# Solar_Charger_Board.net
KiCad netlist of a schematic drawn in EAGLE
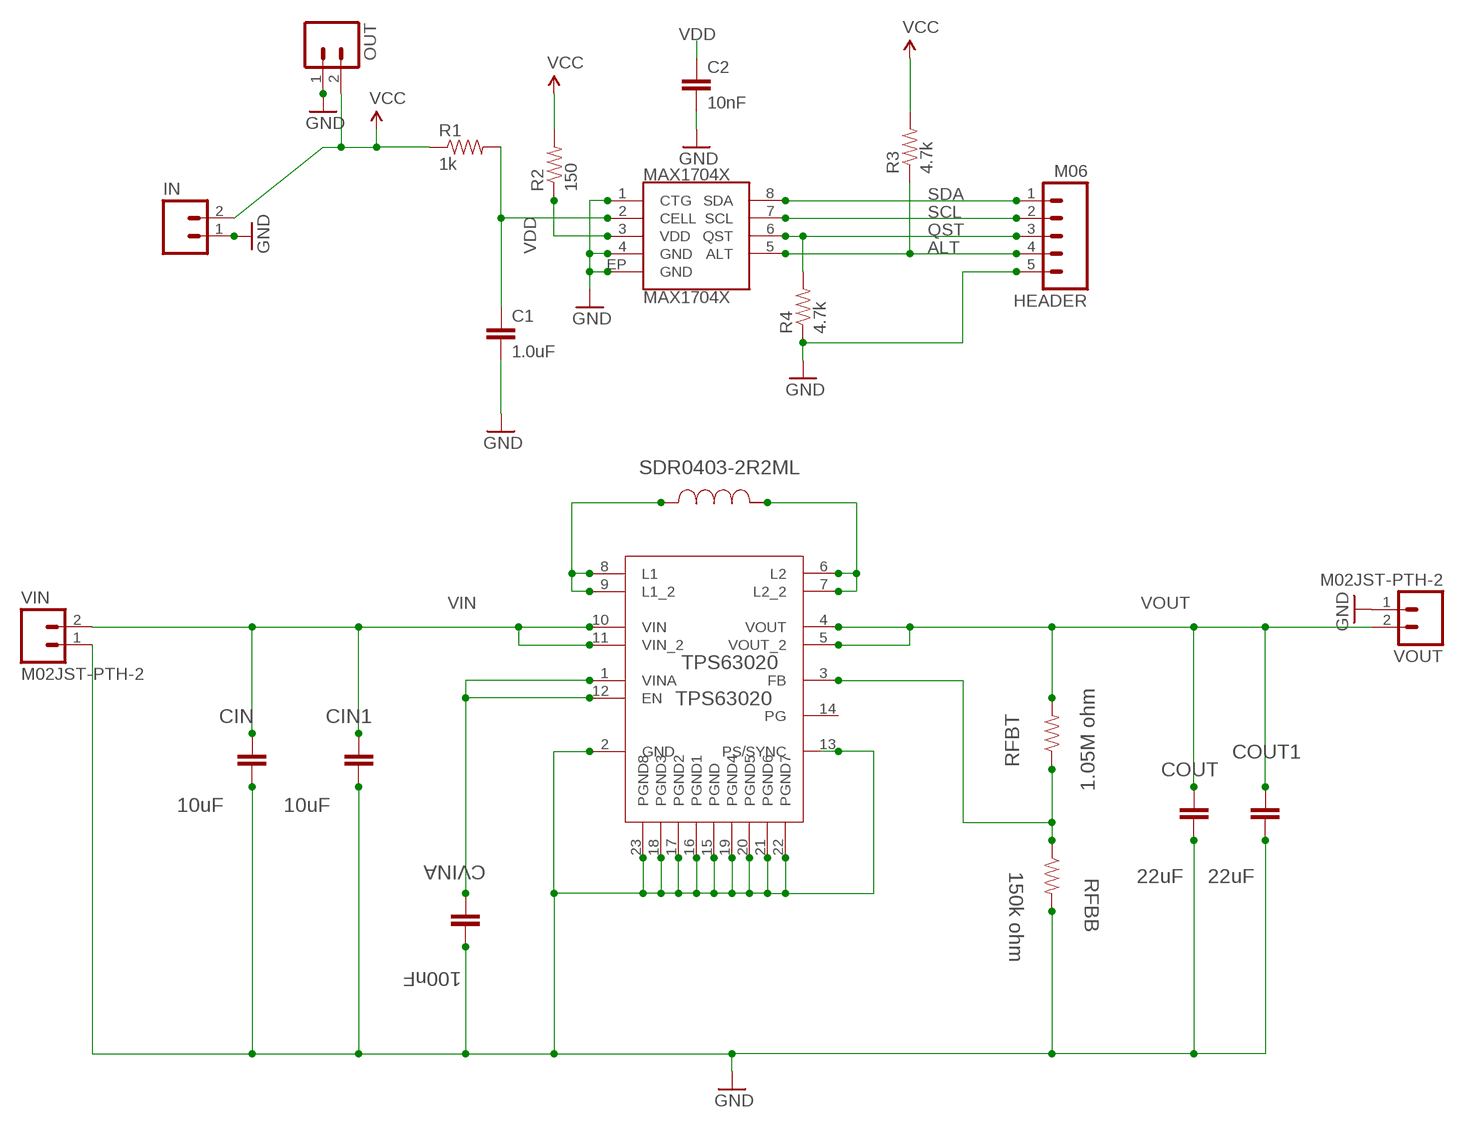
[diagram p0: schematic, sheet 1]

(export (version "E")
  (design (tool "Eeschema 10.0.6"))
  (components
    (comp (ref "C1")
      (value "1.0uF")
      (footprint "eagle-import:0805")
      (libsource (lib "eagle-import") (part "1.0UF-25V-+80/-20(0805)"))
    )
    (comp (ref "C2")
      (value "10nF")
      (footprint "eagle-import:0805")
      (libsource (lib "eagle-import") (part "2.2UF-25V-+80/-20(0805)"))
    )
    (comp (ref "CIN")
      (value "10uF")
      (footprint "eagle-import:0805")
      (libsource (lib "eagle-import") (part "CAP0805"))
    )
    (comp (ref "CIN1")
      (value "10uF")
      (footprint "eagle-import:0805")
      (libsource (lib "eagle-import") (part "CAP0805"))
    )
    (comp (ref "COUT")
      (value "22uF")
      (footprint "eagle-import:0805")
      (libsource (lib "eagle-import") (part "CAP0805"))
    )
    (comp (ref "COUT1")
      (value "22uF")
      (footprint "eagle-import:0805")
      (libsource (lib "eagle-import") (part "CAP0805"))
    )
    (comp (ref "CVINA")
      (value "100nF")
      (footprint "eagle-import:0805")
      (libsource (lib "eagle-import") (part "CAP0805"))
    )
    (comp (ref "HEADER")
      (value "M06")
      (footprint "eagle-import:1X05")
      (libsource (lib "eagle-import") (part "M05PTH"))
    )
    (comp (ref "IN")
      (value "input")
      (footprint "eagle-import:JST-2-PTH")
      (libsource (lib "eagle-import") (part "M02JST-PTH-2"))
    )
    (comp (ref "L1")
      (value "SDR0403-2R2ML")
      (footprint "eagle-import:SDR0403")
      (libsource (lib "eagle-import") (part "SDR0403-2R2ML"))
    )
    (comp (ref "MAX1704X")
      (value "MAX1704X")
      (footprint "eagle-import:TDFN-8")
      (libsource (lib "eagle-import") (part "MAX1704X"))
    )
    (comp (ref "OUT")
      (value "M02JST-PTH-2")
      (footprint "eagle-import:JST-2-PTH")
      (libsource (lib "eagle-import") (part "M02JST-PTH-2"))
    )
    (comp (ref "R1")
      (value "1k")
      (footprint "eagle-import:0805")
      (libsource (lib "eagle-import") (part "RESISTOR0805-RES"))
    )
    (comp (ref "R2")
      (value "150")
      (footprint "eagle-import:0805")
      (libsource (lib "eagle-import") (part "RESISTOR0805-RES"))
    )
    (comp (ref "R3")
      (value "4.7k")
      (footprint "eagle-import:0805")
      (libsource (lib "eagle-import") (part "RESISTOR0805-RES"))
    )
    (comp (ref "R4")
      (value "4.7k")
      (footprint "eagle-import:0805")
      (libsource (lib "eagle-import") (part "RESISTOR0805-RES"))
    )
    (comp (ref "RFBB")
      (value "150k ohm")
      (footprint "eagle-import:0805")
      (libsource (lib "eagle-import") (part "RESISTOR0805-RES"))
    )
    (comp (ref "RFBT")
      (value "1.05M ohm")
      (footprint "eagle-import:0805")
      (libsource (lib "eagle-import") (part "RESISTOR0805-RES"))
    )
    (comp (ref "TPS63020")
      (value "TPS63020")
      (footprint "eagle-import:QFN14-3X4MM")
      (libsource (lib "eagle-import") (part "TPS63020"))
    )
    (comp (ref "VIN")
      (value "M02JST-PTH-2")
      (footprint "eagle-import:JST-2-PTH")
      (libsource (lib "eagle-import") (part "M02JST-PTH-2"))
    )
    (comp (ref "VOUT")
      (value "M02JST-PTH-2")
      (footprint "eagle-import:JST-2-PTH")
      (libsource (lib "eagle-import") (part "M02JST-PTH-2"))
    )
  )
  (nets
    (net (code "1") (name "/ALT") (class "Default")
      (node (ref "HEADER") (pin "4") (pinfunction "4_4") (pintype "passive"))
      (node (ref "MAX1704X") (pin "5") (pinfunction "ALT_5") (pintype "bidirectional"))
      (node (ref "R3") (pin "1") (pinfunction "1_1") (pintype "passive"))
    )
    (net (code "2") (name "/QST") (class "Default")
      (node (ref "HEADER") (pin "3") (pinfunction "3_3") (pintype "passive"))
      (node (ref "MAX1704X") (pin "6") (pinfunction "QST_6") (pintype "bidirectional"))
      (node (ref "R4") (pin "2") (pinfunction "2_2") (pintype "passive"))
    )
    (net (code "3") (name "/SCL") (class "Default")
      (node (ref "HEADER") (pin "2") (pinfunction "2_2") (pintype "passive"))
      (node (ref "MAX1704X") (pin "7") (pinfunction "SCL_7") (pintype "bidirectional"))
    )
    (net (code "4") (name "/SDA") (class "Default")
      (node (ref "HEADER") (pin "1") (pinfunction "1_1") (pintype "passive"))
      (node (ref "MAX1704X") (pin "8") (pinfunction "SDA_8") (pintype "bidirectional"))
    )
    (net (code "5") (name "/VDD") (class "Default")
      (node (ref "C2") (pin "1") (pinfunction "1_1") (pintype "passive"))
      (node (ref "MAX1704X") (pin "3") (pinfunction "VDD_3") (pintype "bidirectional"))
      (node (ref "R2") (pin "1") (pinfunction "1_1") (pintype "passive"))
    )
    (net (code "6") (name "/VIN") (class "Default")
      (node (ref "CIN") (pin "1") (pinfunction "1_1") (pintype "passive"))
      (node (ref "CIN1") (pin "1") (pinfunction "1_1") (pintype "passive"))
      (node (ref "TPS63020") (pin "10") (pinfunction "VIN_10") (pintype "bidirectional"))
      (node (ref "TPS63020") (pin "11") (pinfunction "VIN_2_11") (pintype "bidirectional"))
      (node (ref "VIN") (pin "2") (pinfunction "2_2") (pintype "passive"))
    )
    (net (code "7") (name "/VOUT") (class "Default")
      (node (ref "COUT") (pin "1") (pinfunction "1_1") (pintype "passive"))
      (node (ref "COUT1") (pin "1") (pinfunction "1_1") (pintype "passive"))
      (node (ref "RFBT") (pin "2") (pinfunction "2_2") (pintype "passive"))
      (node (ref "TPS63020") (pin "4") (pinfunction "VOUT_4") (pintype "bidirectional"))
      (node (ref "TPS63020") (pin "5") (pinfunction "VOUT_2_5") (pintype "bidirectional"))
      (node (ref "VOUT") (pin "2") (pinfunction "2_2") (pintype "passive"))
    )
    (net (code "8") (name "GND") (class "Default")
      (node (ref "C1") (pin "2") (pinfunction "2_2") (pintype "passive"))
      (node (ref "C2") (pin "2") (pinfunction "2_2") (pintype "passive"))
      (node (ref "CIN") (pin "2") (pinfunction "2_2") (pintype "passive"))
      (node (ref "CIN1") (pin "2") (pinfunction "2_2") (pintype "passive"))
      (node (ref "COUT") (pin "2") (pinfunction "2_2") (pintype "passive"))
      (node (ref "COUT1") (pin "2") (pinfunction "2_2") (pintype "passive"))
      (node (ref "CVINA") (pin "2") (pinfunction "2_2") (pintype "passive"))
      (node (ref "HEADER") (pin "5") (pinfunction "5_5") (pintype "passive"))
      (node (ref "IN") (pin "1") (pinfunction "1_1") (pintype "passive"))
      (node (ref "MAX1704X") (pin "1") (pinfunction "CTG_1") (pintype "bidirectional"))
      (node (ref "MAX1704X") (pin "4") (pinfunction "GND_4") (pintype "bidirectional"))
      (node (ref "MAX1704X") (pin "EP") (pinfunction "GND_EP") (pintype "bidirectional"))
      (node (ref "OUT") (pin "1") (pinfunction "1_1") (pintype "passive"))
      (node (ref "R4") (pin "1") (pinfunction "1_1") (pintype "passive"))
      (node (ref "RFBB") (pin "2") (pinfunction "2_2") (pintype "passive"))
      (node (ref "TPS63020") (pin "13") (pinfunction "PS/SYNC_13") (pintype "bidirectional"))
      (node (ref "TPS63020") (pin "15") (pinfunction "PGND_15") (pintype "bidirectional"))
      (node (ref "TPS63020") (pin "16") (pinfunction "PGND1_16") (pintype "bidirectional"))
      (node (ref "TPS63020") (pin "17") (pinfunction "PGND2_17") (pintype "bidirectional"))
      (node (ref "TPS63020") (pin "18") (pinfunction "PGND3_18") (pintype "bidirectional"))
      (node (ref "TPS63020") (pin "19") (pinfunction "PGND4_19") (pintype "bidirectional"))
      (node (ref "TPS63020") (pin "2") (pinfunction "GND_2") (pintype "bidirectional"))
      (node (ref "TPS63020") (pin "20") (pinfunction "PGND5_20") (pintype "bidirectional"))
      (node (ref "TPS63020") (pin "21") (pinfunction "PGND6_21") (pintype "bidirectional"))
      (node (ref "TPS63020") (pin "22") (pinfunction "PGND7_22") (pintype "bidirectional"))
      (node (ref "TPS63020") (pin "23") (pinfunction "PGND8_23") (pintype "bidirectional"))
      (node (ref "VIN") (pin "1") (pinfunction "1_1") (pintype "passive"))
      (node (ref "VOUT") (pin "1") (pinfunction "1_1") (pintype "passive"))
    )
    (net (code "9") (name "Net-(MAX1704X-CELL)") (class "Default")
      (node (ref "C1") (pin "1") (pinfunction "1_1") (pintype "passive"))
      (node (ref "MAX1704X") (pin "2") (pinfunction "CELL_2") (pintype "bidirectional"))
      (node (ref "R1") (pin "2") (pinfunction "2_2") (pintype "passive"))
    )
    (net (code "10") (name "Net-(TPS63020-EN)") (class "Default")
      (node (ref "CVINA") (pin "1") (pinfunction "1_1") (pintype "passive"))
      (node (ref "TPS63020") (pin "1") (pinfunction "VINA_1") (pintype "bidirectional"))
      (node (ref "TPS63020") (pin "12") (pinfunction "EN_12") (pintype "bidirectional"))
    )
    (net (code "11") (name "Net-(TPS63020-FB)") (class "Default")
      (node (ref "RFBB") (pin "1") (pinfunction "1_1") (pintype "passive"))
      (node (ref "RFBT") (pin "1") (pinfunction "1_1") (pintype "passive"))
      (node (ref "TPS63020") (pin "3") (pinfunction "FB_3") (pintype "bidirectional"))
    )
    (net (code "12") (name "Net-(TPS63020-L1)") (class "Default")
      (node (ref "L1") (pin "1") (pinfunction "1_1") (pintype "passive"))
      (node (ref "TPS63020") (pin "8") (pinfunction "L1_8") (pintype "bidirectional"))
      (node (ref "TPS63020") (pin "9") (pinfunction "L1_2_9") (pintype "bidirectional"))
    )
    (net (code "13") (name "Net-(TPS63020-L2)") (class "Default")
      (node (ref "L1") (pin "2") (pinfunction "2_2") (pintype "passive"))
      (node (ref "TPS63020") (pin "6") (pinfunction "L2_6") (pintype "bidirectional"))
      (node (ref "TPS63020") (pin "7") (pinfunction "L2_2_7") (pintype "bidirectional"))
    )
    (net (code "14") (name "VCC") (class "Default")
      (node (ref "IN") (pin "2") (pinfunction "2_2") (pintype "passive"))
      (node (ref "OUT") (pin "2") (pinfunction "2_2") (pintype "passive"))
      (node (ref "R1") (pin "1") (pinfunction "1_1") (pintype "passive"))
      (node (ref "R2") (pin "2") (pinfunction "2_2") (pintype "passive"))
      (node (ref "R3") (pin "2") (pinfunction "2_2") (pintype "passive"))
    )
    (net (code "15") (name "unconnected-(TPS63020-PG-Pad14)") (class "Default")
      (node (ref "TPS63020") (pin "14") (pinfunction "PG_14") (pintype "bidirectional"))
    )
  )
)
